# harp_behavior_speaker_v1_1.net
KiCad netlist of a schematic drawn in EAGLE
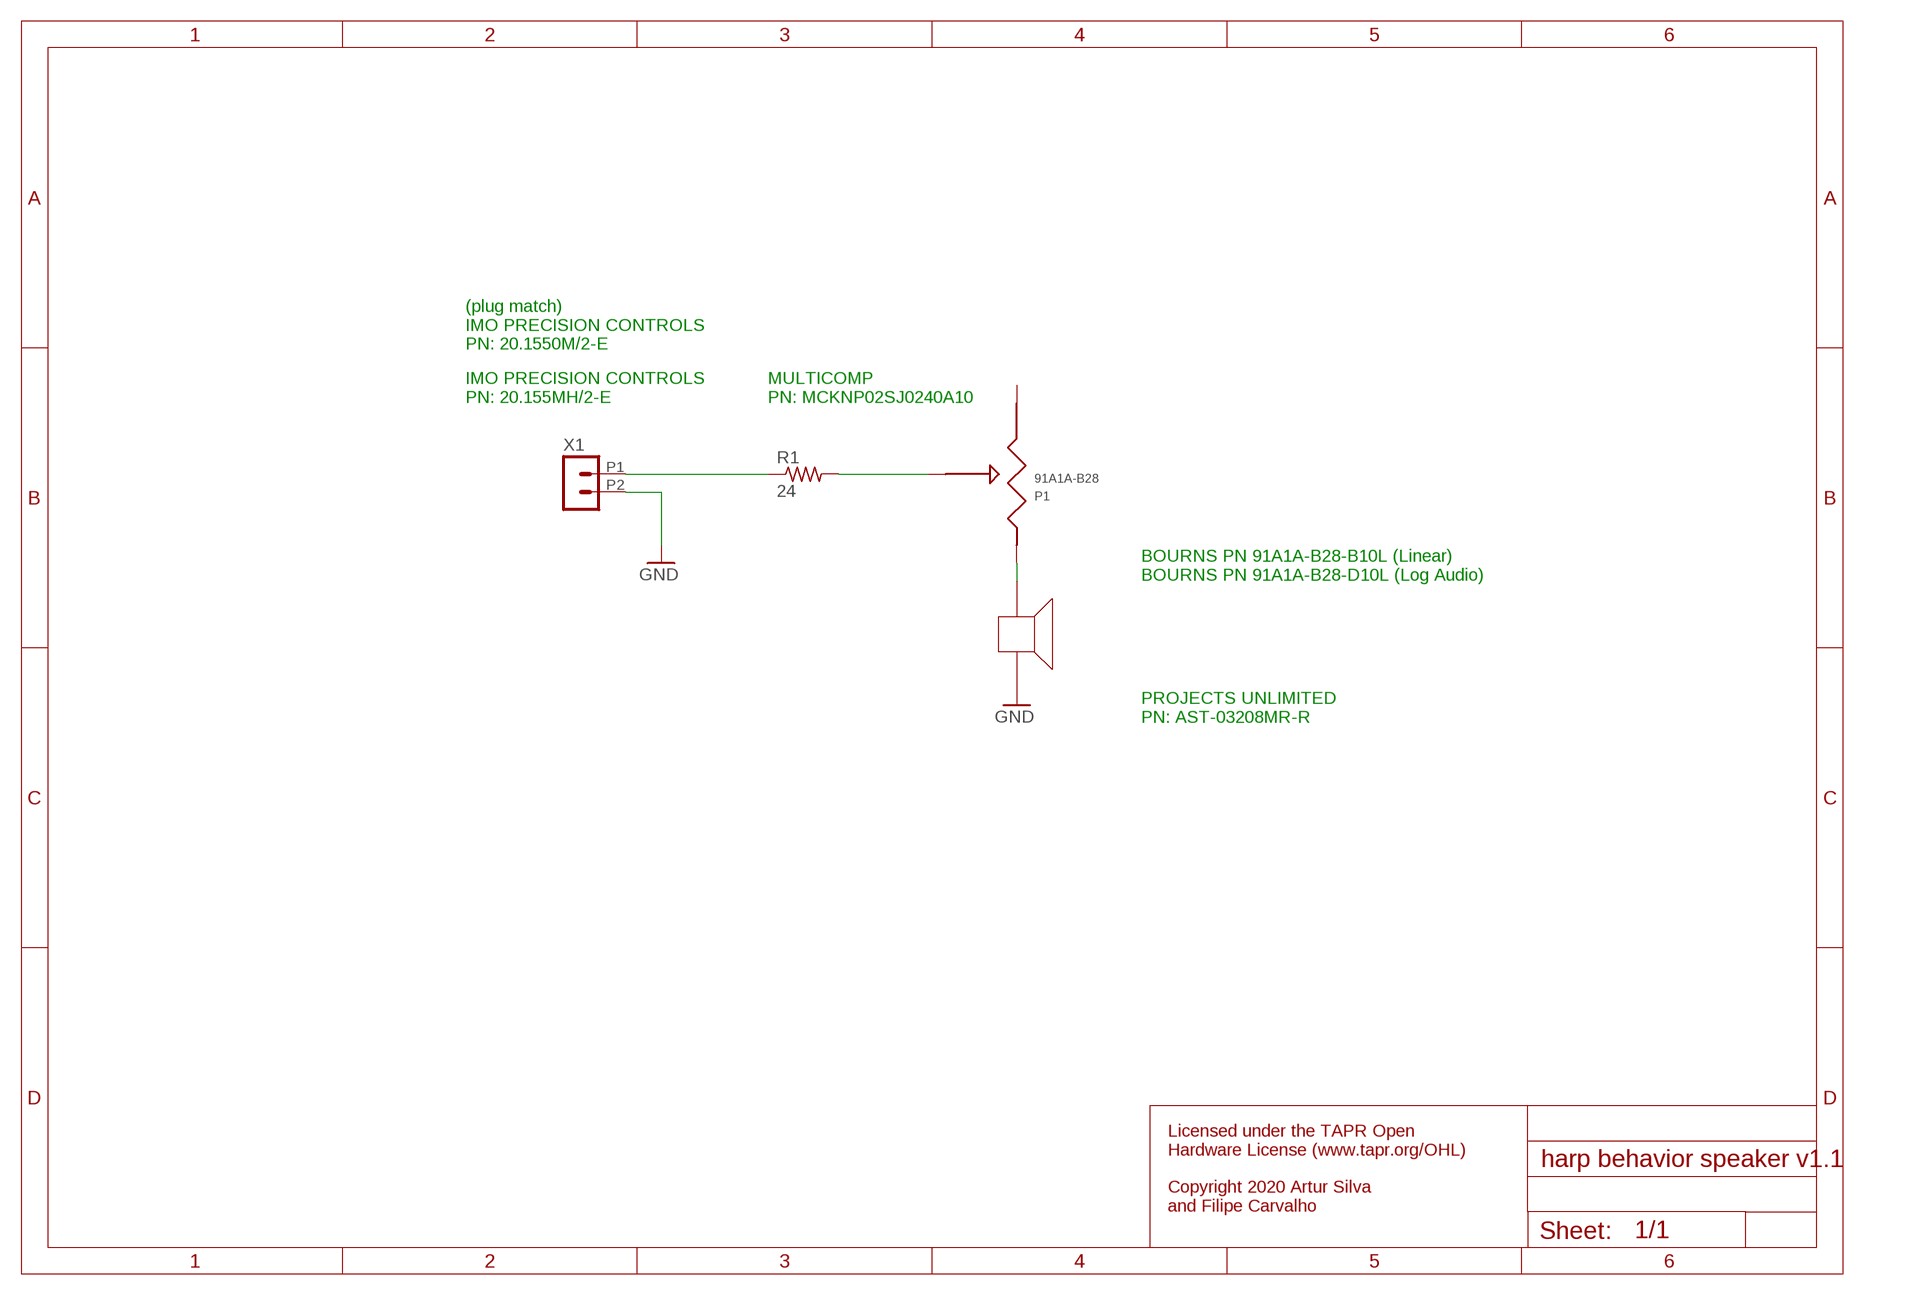
[diagram p0: schematic, sheet 1]

(export (version "E")
  (design (tool "Eeschema 10.0.6"))
  (components
    (comp (ref "P1")
      (value "91A1A-B28")
      (footprint "eagle-import:MODEL91")
      (libsource (lib "eagle-import") (part "91A1A-B28"))
    )
    (comp (ref "R1")
      (value "24")
      (footprint "eagle-import:0617_22")
      (libsource (lib "eagle-import") (part "R-US_0617/22"))
    )
    (comp (ref "X1")
      (value "CON_3.5MM_1X2")
      (footprint "eagle-import:CON_3.5MM_1X2")
      (libsource (lib "eagle-import") (part "CON_3.5MM_1X2"))
    )
  )
  (nets
    (net (code "1") (name "GND") (class "Default")
      (node (ref "X1") (pin "P2") (pinfunction "2_P2") (pintype "passive"))
    )
    (net (code "2") (name "Net-(P1-2)") (class "Default")
      (node (ref "P1") (pin "P$2") (pinfunction "2_P$2") (pintype "bidirectional"))
      (node (ref "R1") (pin "2") (pinfunction "2_2") (pintype "passive"))
    )
    (net (code "3") (name "Net-(X1-1)") (class "Default")
      (node (ref "R1") (pin "1") (pinfunction "1_1") (pintype "passive"))
      (node (ref "X1") (pin "P1") (pinfunction "1_P1") (pintype "passive"))
    )
    (net (code "4") (name "unconnected-(P1-1CCW-PadP$1)") (class "Default")
      (node (ref "P1") (pin "P$1") (pinfunction "1CCW_P$1") (pintype "bidirectional"))
    )
    (net (code "5") (name "unconnected-(P1-3-PadP$3)") (class "Default")
      (node (ref "P1") (pin "P$3") (pinfunction "3_P$3") (pintype "bidirectional"))
    )
  )
)
